# New.net
KiCad netlist of a schematic drawn in EAGLE
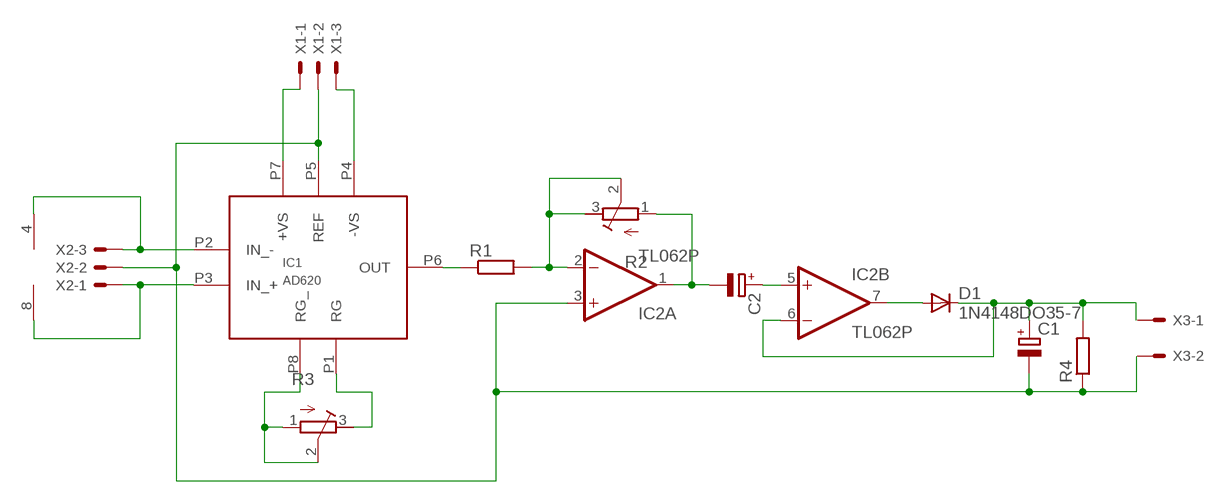
[diagram p0: schematic, sheet 1]

(export (version "E")
  (design (tool "Eeschema 10.0.6"))
  (components
    (comp (ref "C1")
      (value "CPOL-EUB45181A")
      (footprint "eagle-import:B45181A")
      (libsource (lib "eagle-import") (part "CPOL-EUB45181A"))
    )
    (comp (ref "C2")
      (value "CPOL-EUB45181A")
      (footprint "eagle-import:B45181A")
      (libsource (lib "eagle-import") (part "CPOL-EUB45181A"))
    )
    (comp (ref "D1")
      (value "1N4148DO35-7")
      (footprint "eagle-import:DO35-7")
      (libsource (lib "eagle-import") (part "1N4148DO35-7"))
    )
    (comp (ref "IC1")
      (value "AD620")
      (footprint "eagle-import:DIL8")
      (libsource (lib "eagle-import") (part "AD620"))
    )
    (comp (ref "IC2")
      (value "TL062P")
      (footprint "eagle-import:DIL08")
      (libsource (lib "eagle-import") (part "TL062P"))
    )
    (comp (ref "R1")
      (value "R-EU_0207/10")
      (footprint "eagle-import:0207_10")
      (libsource (lib "eagle-import") (part "R-EU_0207/10"))
    )
    (comp (ref "R2")
      (value "R-TRIMM64Z")
      (footprint "eagle-import:RTRIM64Z")
      (libsource (lib "eagle-import") (part "R-TRIMM64Z"))
    )
    (comp (ref "R3")
      (value "R-TRIMM64Z")
      (footprint "eagle-import:RTRIM64Z")
      (libsource (lib "eagle-import") (part "R-TRIMM64Z"))
    )
    (comp (ref "R4")
      (value "R-EU_0207/10")
      (footprint "eagle-import:0207_10")
      (libsource (lib "eagle-import") (part "R-EU_0207/10"))
    )
    (comp (ref "X1")
      (value "KK-156-3")
      (footprint "eagle-import:KK-156-3")
      (libsource (lib "eagle-import") (part "KK-156-3"))
    )
    (comp (ref "X2")
      (value "KK-156-3")
      (footprint "eagle-import:KK-156-3")
      (libsource (lib "eagle-import") (part "KK-156-3"))
    )
    (comp (ref "X3")
      (value "KK-156-2")
      (footprint "eagle-import:KK-156-2")
      (libsource (lib "eagle-import") (part "KK-156-2"))
    )
  )
  (nets
    (net (code "1") (name "Net-(IC1-+VS)") (class "Default")
      (node (ref "IC1") (pin "P7") (pinfunction "+VS_P7") (pintype "power_in"))
      (node (ref "X1") (pin "1") (pinfunction "S_1") (pintype "passive"))
    )
    (net (code "2") (name "Net-(IC1--VS)") (class "Default")
      (node (ref "IC1") (pin "P4") (pinfunction "-VS_P4") (pintype "power_in"))
      (node (ref "X1") (pin "3") (pinfunction "S_3") (pintype "passive"))
    )
    (net (code "3") (name "Net-(IC1-IN_+)") (class "Default")
      (node (ref "IC1") (pin "P3") (pinfunction "IN_+_P3") (pintype "input"))
      (node (ref "IC2") (pin "8") (pinfunction "V+_8") (pintype "power_in"))
      (node (ref "X2") (pin "1") (pinfunction "S_1") (pintype "passive"))
    )
    (net (code "4") (name "Net-(IC1-IN_-)") (class "Default")
      (node (ref "IC1") (pin "P2") (pinfunction "IN_-_P2") (pintype "input"))
      (node (ref "IC2") (pin "4") (pinfunction "V-_4") (pintype "power_in"))
      (node (ref "X2") (pin "3") (pinfunction "S_3") (pintype "passive"))
    )
    (net (code "5") (name "Net-(IC1-OUT)") (class "Default")
      (node (ref "IC1") (pin "P6") (pinfunction "OUT_P6") (pintype "output"))
      (node (ref "R1") (pin "1") (pinfunction "1_1") (pintype "passive"))
    )
    (net (code "6") (name "Net-(IC1-REF)") (class "Default")
      (node (ref "C1") (pin "-") (pinfunction "-_-") (pintype "passive"))
      (node (ref "IC1") (pin "P5") (pinfunction "REF_P5") (pintype "power_in"))
      (node (ref "IC2") (pin "3") (pinfunction "+IN_3") (pintype "input"))
      (node (ref "R4") (pin "1") (pinfunction "1_1") (pintype "passive"))
      (node (ref "X1") (pin "2") (pinfunction "S_2") (pintype "passive"))
      (node (ref "X2") (pin "2") (pinfunction "S_2") (pintype "passive"))
    )
    (net (code "7") (name "Net-(IC1-RG)") (class "Default")
      (node (ref "IC1") (pin "P1") (pinfunction "RG_P1") (pintype "input"))
      (node (ref "R3") (pin "3") (pinfunction "E_3") (pintype "passive"))
    )
    (net (code "8") (name "Net-(IC1-RG_)") (class "Default")
      (node (ref "IC1") (pin "P8") (pinfunction "RG__P8") (pintype "input"))
      (node (ref "R3") (pin "1") (pinfunction "A_1") (pintype "passive"))
      (node (ref "R3") (pin "2") (pinfunction "S_2") (pintype "passive"))
    )
    (net (code "9") (name "Net-(IC2A--IN)") (class "Default")
      (node (ref "IC2") (pin "2") (pinfunction "-IN_2") (pintype "input"))
      (node (ref "R1") (pin "2") (pinfunction "2_2") (pintype "passive"))
      (node (ref "R2") (pin "2") (pinfunction "S_2") (pintype "passive"))
      (node (ref "R2") (pin "3") (pinfunction "E_3") (pintype "passive"))
    )
    (net (code "10") (name "Net-(IC2A-OUT)") (class "Default")
      (node (ref "C2") (pin "-") (pinfunction "-_-") (pintype "passive"))
      (node (ref "IC2") (pin "1") (pinfunction "OUT_1") (pintype "output"))
      (node (ref "R2") (pin "1") (pinfunction "A_1") (pintype "passive"))
    )
    (net (code "11") (name "Net-(IC2B-+IN)") (class "Default")
      (node (ref "C2") (pin "+") (pinfunction "+_+") (pintype "passive"))
      (node (ref "IC2") (pin "5") (pinfunction "+IN_5") (pintype "input"))
    )
    (net (code "12") (name "Net-(IC2B--IN)") (class "Default")
      (node (ref "C1") (pin "+") (pinfunction "+_+") (pintype "passive"))
      (node (ref "D1") (pin "C") (pinfunction "C_C") (pintype "passive"))
      (node (ref "IC2") (pin "6") (pinfunction "-IN_6") (pintype "input"))
      (node (ref "R4") (pin "2") (pinfunction "2_2") (pintype "passive"))
    )
    (net (code "13") (name "Net-(IC2B-OUT)") (class "Default")
      (node (ref "D1") (pin "A") (pinfunction "A_A") (pintype "passive"))
      (node (ref "IC2") (pin "7") (pinfunction "OUT_7") (pintype "output"))
    )
    (net (code "14") (name "unconnected-(X3A-S-Pad1)") (class "Default")
      (node (ref "X3") (pin "1") (pinfunction "S_1") (pintype "passive"))
    )
    (net (code "15") (name "unconnected-(X3B-S-Pad2)") (class "Default")
      (node (ref "X3") (pin "2") (pinfunction "S_2") (pintype "passive"))
    )
  )
)
